# LTEbee_adapter_rev1b.net
KiCad netlist of a schematic drawn in EAGLE
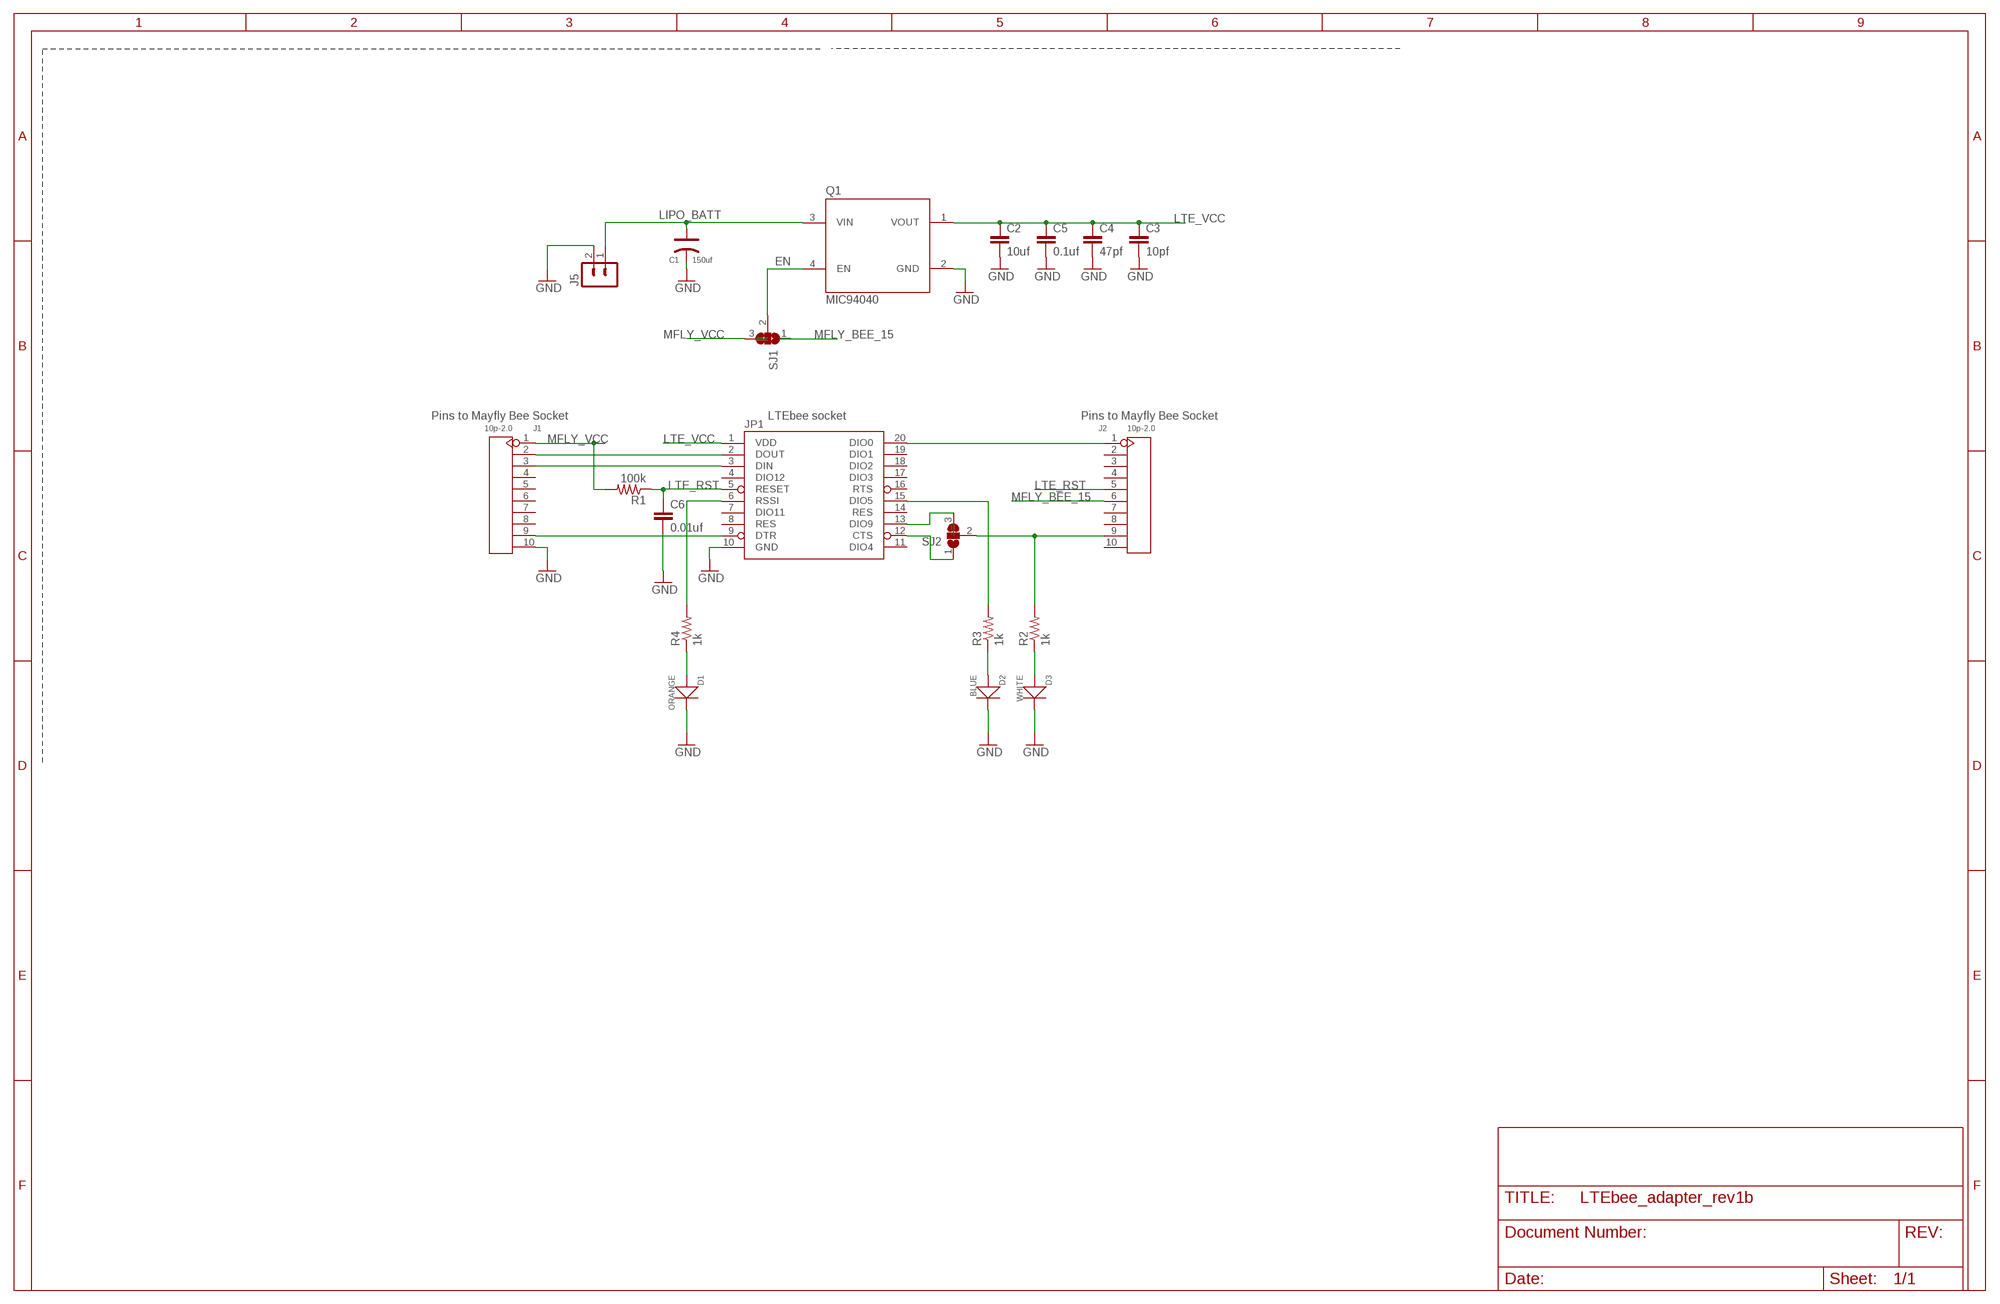
[diagram p0: schematic, sheet 1]

(export (version "E")
  (design (tool "Eeschema 10.0.6"))
  (components
    (comp (ref "C1")
      (value "150uf")
      (footprint "eagle-import:AVX-B")
      (fields (field (name "MPN") "TAJB107M010#NJ"))
      (libsource (lib "eagle-import") (part "TANTALUM-SMD-100UF-10V(AVX-B)"))
    )
    (comp (ref "C2")
      (value "10uf")
      (footprint "eagle-import:0402-CAP")
      (libsource (lib "eagle-import") (part "CAP0402-CAP"))
    )
    (comp (ref "C3")
      (value "10pf")
      (footprint "eagle-import:0402-CAP")
      (libsource (lib "eagle-import") (part "CAP0402-CAP"))
    )
    (comp (ref "C4")
      (value "47pf")
      (footprint "eagle-import:0402-CAP")
      (libsource (lib "eagle-import") (part "CAP0402-CAP"))
    )
    (comp (ref "C5")
      (value "0.1uf")
      (footprint "eagle-import:0402-CAP")
      (libsource (lib "eagle-import") (part "CAP0402-CAP"))
    )
    (comp (ref "C6")
      (value "0.01uf")
      (footprint "eagle-import:0402-CAP")
      (libsource (lib "eagle-import") (part "CAP0402-CAP"))
    )
    (comp (ref "D1")
      (value "ORANGE")
      (footprint "eagle-import:SOD-523")
      (libsource (lib "eagle-import") (part "DIODE'0603'"))
    )
    (comp (ref "D2")
      (value "BLUE")
      (footprint "eagle-import:SOD-523")
      (libsource (lib "eagle-import") (part "DIODE'0603'"))
    )
    (comp (ref "D3")
      (value "WHITE")
      (footprint "eagle-import:SOD-523")
      (libsource (lib "eagle-import") (part "DIODE'0603'"))
    )
    (comp (ref "J1")
      (value "10p-2.0")
      (footprint "eagle-import:H10-2.0")
      (fields (field (name "MPN") "F243-1110A1BSUA1"))
      (libsource (lib "eagle-import") (part "DIP-BLACK-FEMALE-HEADER-VERT(10P-2.0)"))
    )
    (comp (ref "J2")
      (value "10p-2.0")
      (footprint "eagle-import:H10-2.0")
      (fields (field (name "MPN") "F243-1110A1BSUA1"))
      (libsource (lib "eagle-import") (part "DIP-BLACK-FEMALE-HEADER-VERT(10P-2.0)"))
    )
    (comp (ref "J5")
      (value "B2B-PH-K-S")
      (footprint "eagle-import:B2B-PH-K-S")
      (libsource (lib "eagle-import") (part "B2B-PH-K-S"))
    )
    (comp (ref "JP1")
      (value "XBEE-1B1")
      (footprint "eagle-import:XBEE-1")
      (libsource (lib "eagle-import") (part "XBEE-1B1"))
    )
    (comp (ref "Q1")
      (value "MIC94040")
      (footprint "eagle-import:MLF4")
      (libsource (lib "eagle-import") (part "MIC94040"))
    )
    (comp (ref "R1")
      (value "100k")
      (footprint "eagle-import:0603-RES")
      (libsource (lib "eagle-import") (part "RESISTOR0603"))
    )
    (comp (ref "R2")
      (value "1k")
      (footprint "eagle-import:0603-RES")
      (libsource (lib "eagle-import") (part "RESISTOR0603"))
    )
    (comp (ref "R3")
      (value "1k")
      (footprint "eagle-import:0603-RES")
      (libsource (lib "eagle-import") (part "RESISTOR0603"))
    )
    (comp (ref "R4")
      (value "1k")
      (footprint "eagle-import:0603-RES")
      (libsource (lib "eagle-import") (part "RESISTOR0603"))
    )
    (comp (ref "SJ1")
      (value "SJ2W")
      (footprint "eagle-import:SJ_2")
      (libsource (lib "eagle-import") (part "SJ2W"))
    )
    (comp (ref "SJ2")
      (value "SJ2W")
      (footprint "eagle-import:SJ_2")
      (libsource (lib "eagle-import") (part "SJ2W"))
    )
  )
  (nets
    (net (code "1") (name "/EN") (class "Default")
      (node (ref "Q1") (pin "4") (pinfunction "EN_4") (pintype "bidirectional"))
      (node (ref "SJ1") (pin "2") (pinfunction "2_2") (pintype "passive"))
    )
    (net (code "2") (name "/LIPO_BATT") (class "Default")
      (node (ref "C1") (pin "+") (pinfunction "+_+") (pintype "passive"))
      (node (ref "J5") (pin "1") (pinfunction "1_1") (pintype "passive"))
      (node (ref "Q1") (pin "3") (pinfunction "VIN_3") (pintype "bidirectional"))
    )
    (net (code "3") (name "/LTE_RST") (class "Default")
      (node (ref "C6") (pin "1") (pinfunction "1_1") (pintype "passive"))
      (node (ref "J2") (pin "5") (pinfunction "5_5") (pintype "bidirectional"))
      (node (ref "JP1") (pin "5") (pinfunction "RESET_5") (pintype "input"))
      (node (ref "R1") (pin "1") (pinfunction "1_1") (pintype "passive"))
    )
    (net (code "4") (name "/LTE_VCC") (class "Default")
      (node (ref "C2") (pin "1") (pinfunction "1_1") (pintype "passive"))
      (node (ref "C3") (pin "1") (pinfunction "1_1") (pintype "passive"))
      (node (ref "C4") (pin "1") (pinfunction "1_1") (pintype "passive"))
      (node (ref "C5") (pin "1") (pinfunction "1_1") (pintype "passive"))
      (node (ref "JP1") (pin "1") (pinfunction "VDD_1") (pintype "power_in"))
      (node (ref "Q1") (pin "1") (pinfunction "VOUT_1") (pintype "bidirectional"))
    )
    (net (code "5") (name "/MFLY_BEE_15") (class "Default")
      (node (ref "J2") (pin "6") (pinfunction "6_6") (pintype "bidirectional"))
      (node (ref "SJ1") (pin "1") (pinfunction "1_1") (pintype "passive"))
    )
    (net (code "6") (name "/MFLY_VCC") (class "Default")
      (node (ref "J1") (pin "1") (pinfunction "1_1") (pintype "bidirectional"))
      (node (ref "R1") (pin "2") (pinfunction "2_2") (pintype "passive"))
      (node (ref "SJ1") (pin "3") (pinfunction "3_3") (pintype "passive"))
    )
    (net (code "7") (name "GND") (class "Default")
      (node (ref "C1") (pin "-") (pinfunction "-_-") (pintype "passive"))
      (node (ref "C2") (pin "2") (pinfunction "2_2") (pintype "passive"))
      (node (ref "C3") (pin "2") (pinfunction "2_2") (pintype "passive"))
      (node (ref "C4") (pin "2") (pinfunction "2_2") (pintype "passive"))
      (node (ref "C5") (pin "2") (pinfunction "2_2") (pintype "passive"))
      (node (ref "C6") (pin "2") (pinfunction "2_2") (pintype "passive"))
      (node (ref "D1") (pin "-") (pinfunction "-_-") (pintype "passive"))
      (node (ref "D2") (pin "-") (pinfunction "-_-") (pintype "passive"))
      (node (ref "D3") (pin "-") (pinfunction "-_-") (pintype "passive"))
      (node (ref "J1") (pin "10") (pinfunction "10_10") (pintype "bidirectional"))
      (node (ref "J5") (pin "2") (pinfunction "2_2") (pintype "passive"))
      (node (ref "JP1") (pin "10") (pinfunction "GND_10") (pintype "power_in"))
      (node (ref "Q1") (pin "2") (pinfunction "GND_2") (pintype "bidirectional"))
    )
    (net (code "8") (name "Net-(D1-Pad+)") (class "Default")
      (node (ref "D1") (pin "+") (pinfunction "+_+") (pintype "passive"))
      (node (ref "R4") (pin "1") (pinfunction "1_1") (pintype "passive"))
    )
    (net (code "9") (name "Net-(D2-Pad+)") (class "Default")
      (node (ref "D2") (pin "+") (pinfunction "+_+") (pintype "passive"))
      (node (ref "R3") (pin "1") (pinfunction "1_1") (pintype "passive"))
    )
    (net (code "10") (name "Net-(D3-Pad+)") (class "Default")
      (node (ref "D3") (pin "+") (pinfunction "+_+") (pintype "passive"))
      (node (ref "R2") (pin "1") (pinfunction "1_1") (pintype "passive"))
    )
    (net (code "11") (name "Net-(J2-Pad9)") (class "Default")
      (node (ref "J2") (pin "9") (pinfunction "9_9") (pintype "bidirectional"))
      (node (ref "R2") (pin "2") (pinfunction "2_2") (pintype "passive"))
      (node (ref "SJ2") (pin "2") (pinfunction "2_2") (pintype "passive"))
    )
    (net (code "12") (name "Net-(JP1-CTS)") (class "Default")
      (node (ref "JP1") (pin "12") (pinfunction "CTS_12") (pintype "output"))
      (node (ref "SJ2") (pin "1") (pinfunction "1_1") (pintype "passive"))
    )
    (net (code "13") (name "Net-(JP1-DIN)") (class "Default")
      (node (ref "J1") (pin "3") (pinfunction "3_3") (pintype "bidirectional"))
      (node (ref "JP1") (pin "3") (pinfunction "DIN_3") (pintype "input"))
    )
    (net (code "14") (name "Net-(JP1-DIO0)") (class "Default")
      (node (ref "J2") (pin "1") (pinfunction "1_1") (pintype "bidirectional"))
      (node (ref "JP1") (pin "20") (pinfunction "DIO0_20") (pintype "bidirectional"))
    )
    (net (code "15") (name "Net-(JP1-DIO5)") (class "Default")
      (node (ref "JP1") (pin "15") (pinfunction "DIO5_15") (pintype "bidirectional"))
      (node (ref "R3") (pin "2") (pinfunction "2_2") (pintype "passive"))
    )
    (net (code "16") (name "Net-(JP1-DIO9)") (class "Default")
      (node (ref "JP1") (pin "13") (pinfunction "DIO9_13") (pintype "bidirectional"))
      (node (ref "SJ2") (pin "3") (pinfunction "3_3") (pintype "passive"))
    )
    (net (code "17") (name "Net-(JP1-DOUT)") (class "Default")
      (node (ref "J1") (pin "2") (pinfunction "2_2") (pintype "bidirectional"))
      (node (ref "JP1") (pin "2") (pinfunction "DOUT_2") (pintype "output"))
    )
    (net (code "18") (name "Net-(JP1-DTR)") (class "Default")
      (node (ref "J1") (pin "9") (pinfunction "9_9") (pintype "bidirectional"))
      (node (ref "JP1") (pin "9") (pinfunction "DTR_9") (pintype "bidirectional"))
    )
    (net (code "19") (name "Net-(JP1-RSSI)") (class "Default")
      (node (ref "JP1") (pin "6") (pinfunction "RSSI_6") (pintype "bidirectional"))
      (node (ref "R4") (pin "2") (pinfunction "2_2") (pintype "passive"))
    )
    (net (code "20") (name "unconnected-(J1-Pad4)") (class "Default")
      (node (ref "J1") (pin "4") (pinfunction "4_4") (pintype "bidirectional"))
    )
    (net (code "21") (name "unconnected-(J1-Pad5)") (class "Default")
      (node (ref "J1") (pin "5") (pinfunction "5_5") (pintype "bidirectional"))
    )
    (net (code "22") (name "unconnected-(J1-Pad6)") (class "Default")
      (node (ref "J1") (pin "6") (pinfunction "6_6") (pintype "bidirectional"))
    )
    (net (code "23") (name "unconnected-(J1-Pad7)") (class "Default")
      (node (ref "J1") (pin "7") (pinfunction "7_7") (pintype "bidirectional"))
    )
    (net (code "24") (name "unconnected-(J1-Pad8)") (class "Default")
      (node (ref "J1") (pin "8") (pinfunction "8_8") (pintype "bidirectional"))
    )
    (net (code "25") (name "unconnected-(J2-Pad2)") (class "Default")
      (node (ref "J2") (pin "2") (pinfunction "2_2") (pintype "bidirectional"))
    )
    (net (code "26") (name "unconnected-(J2-Pad3)") (class "Default")
      (node (ref "J2") (pin "3") (pinfunction "3_3") (pintype "bidirectional"))
    )
    (net (code "27") (name "unconnected-(J2-Pad4)") (class "Default")
      (node (ref "J2") (pin "4") (pinfunction "4_4") (pintype "bidirectional"))
    )
    (net (code "28") (name "unconnected-(J2-Pad7)") (class "Default")
      (node (ref "J2") (pin "7") (pinfunction "7_7") (pintype "bidirectional"))
    )
    (net (code "29") (name "unconnected-(J2-Pad8)") (class "Default")
      (node (ref "J2") (pin "8") (pinfunction "8_8") (pintype "bidirectional"))
    )
    (net (code "30") (name "unconnected-(J2-Pad10)") (class "Default")
      (node (ref "J2") (pin "10") (pinfunction "10_10") (pintype "bidirectional"))
    )
    (net (code "31") (name "unconnected-(JP1-DIO1-Pad19)") (class "Default")
      (node (ref "JP1") (pin "19") (pinfunction "DIO1_19") (pintype "bidirectional"))
    )
    (net (code "32") (name "unconnected-(JP1-DIO2-Pad18)") (class "Default")
      (node (ref "JP1") (pin "18") (pinfunction "DIO2_18") (pintype "bidirectional"))
    )
    (net (code "33") (name "unconnected-(JP1-DIO3-Pad17)") (class "Default")
      (node (ref "JP1") (pin "17") (pinfunction "DIO3_17") (pintype "bidirectional"))
    )
    (net (code "34") (name "unconnected-(JP1-DIO4-Pad11)") (class "Default")
      (node (ref "JP1") (pin "11") (pinfunction "DIO4_11") (pintype "bidirectional"))
    )
    (net (code "35") (name "unconnected-(JP1-DIO11-Pad7)") (class "Default")
      (node (ref "JP1") (pin "7") (pinfunction "DIO11_7") (pintype "bidirectional"))
    )
    (net (code "36") (name "unconnected-(JP1-DIO12-Pad4)") (class "Default")
      (node (ref "JP1") (pin "4") (pinfunction "DIO12_4") (pintype "bidirectional"))
    )
    (net (code "37") (name "unconnected-(JP1-RES-Pad8)") (class "Default")
      (node (ref "JP1") (pin "8") (pinfunction "RES_8") (pintype "bidirectional"))
    )
    (net (code "38") (name "unconnected-(JP1-RES-Pad14)") (class "Default")
      (node (ref "JP1") (pin "14") (pinfunction "RES_14") (pintype "bidirectional"))
    )
    (net (code "39") (name "unconnected-(JP1-RTS-Pad16)") (class "Default")
      (node (ref "JP1") (pin "16") (pinfunction "RTS_16") (pintype "input"))
    )
  )
)
